# Base_USB_Camera.net
KiCad netlist of a schematic drawn in Altium Designer
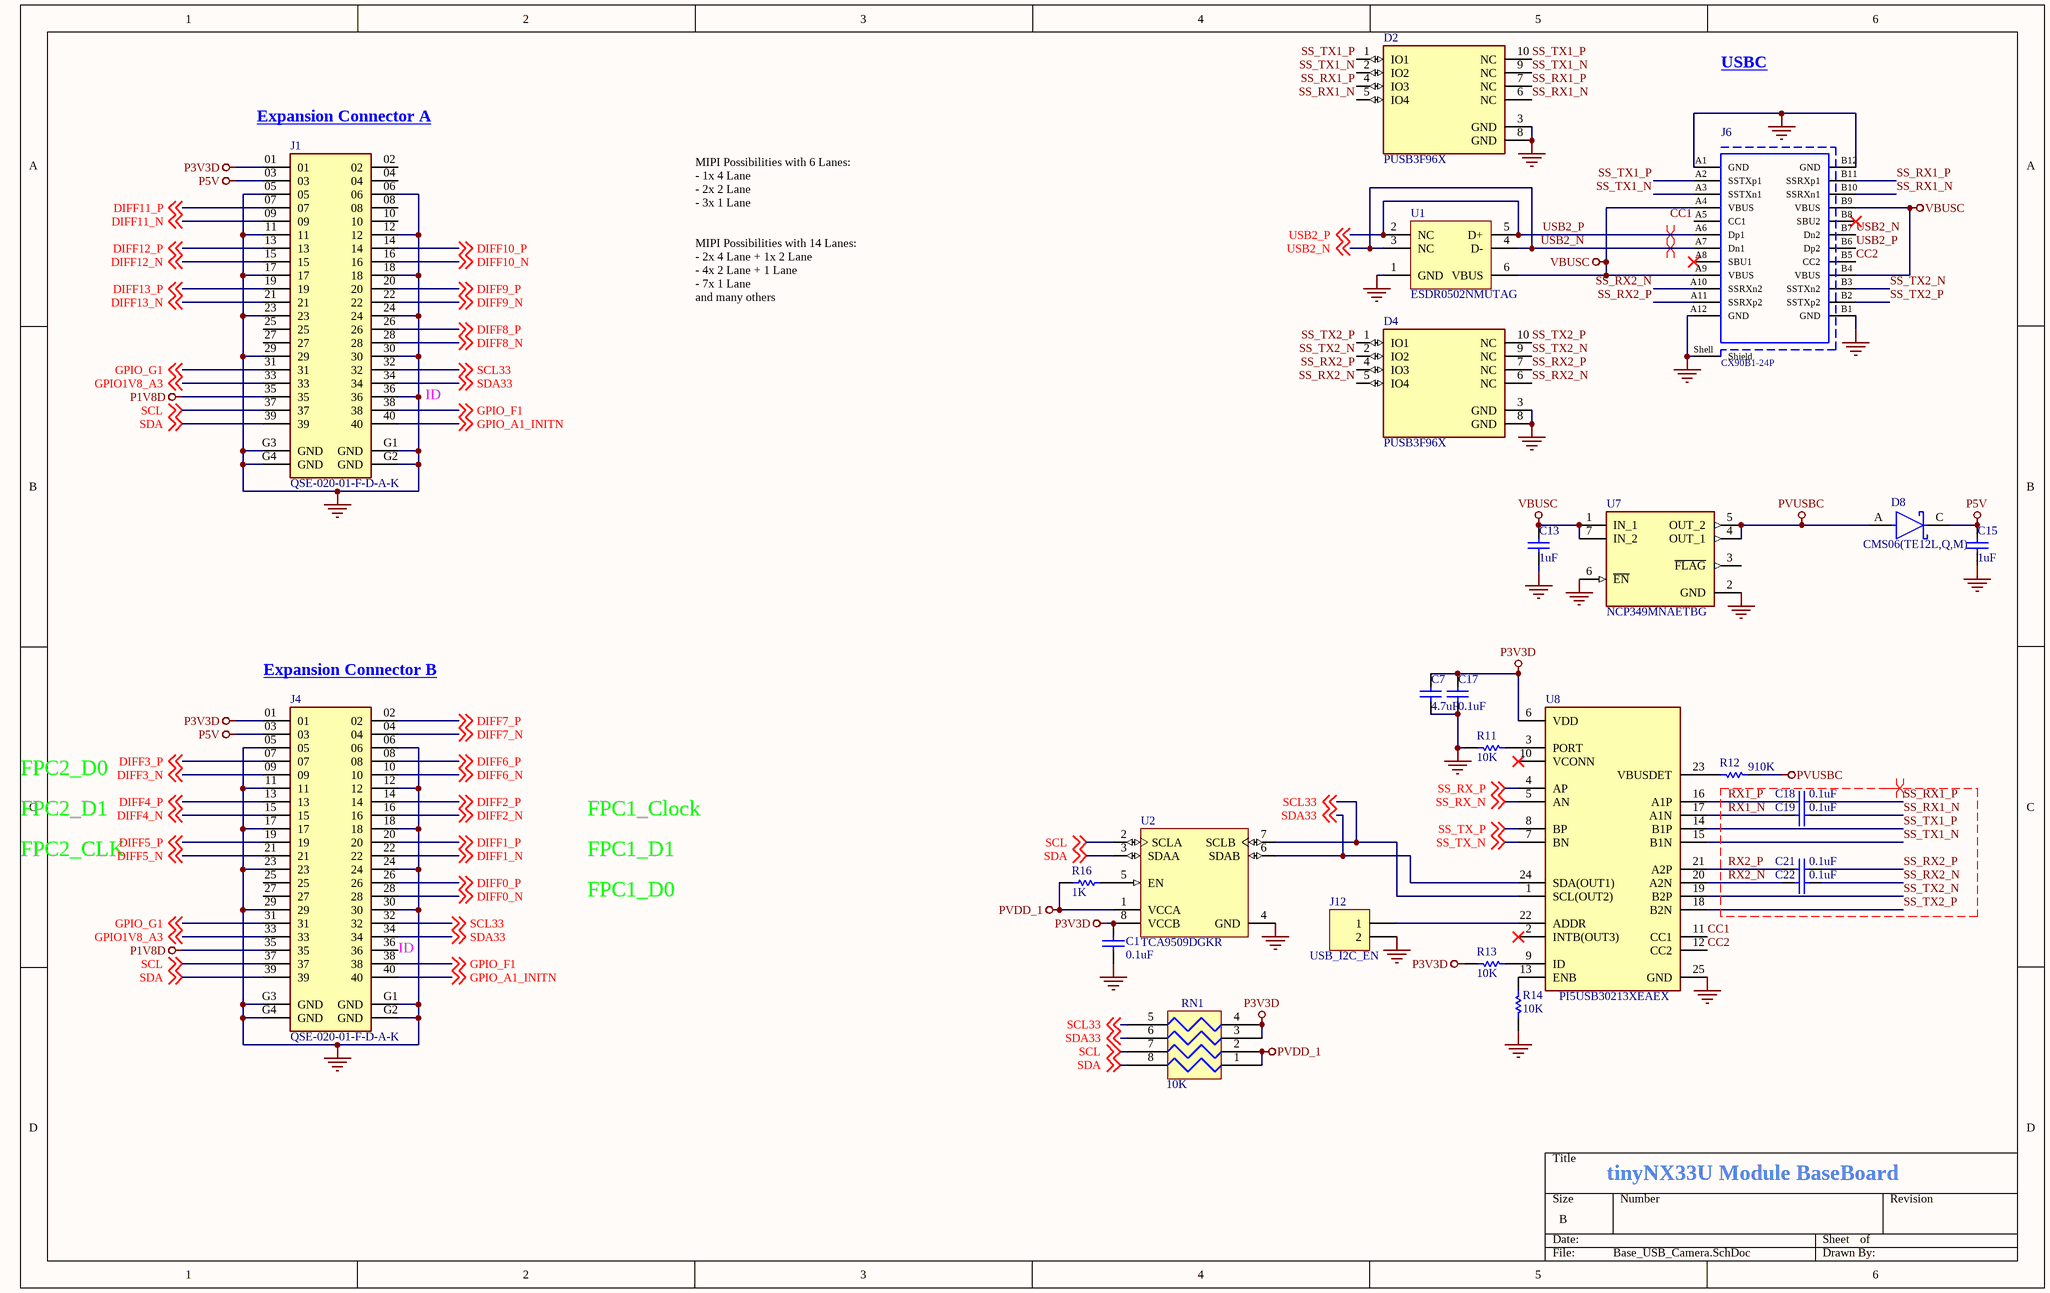
[diagram p0: Base_USB_Camera.SchDoc]

(export (version "E")
  (design (tool "Eeschema 10.0.6"))
  (components
    (comp (ref "C1")
      (value "0.1uF")
      (footprint "CAPC1005X55USR")
      (description "CAP CER 0.1UF 16V X7R 0402")
      (fields
        (field (name "MANUFACTURER PART NUMBER") "CGA2B1X7R1C104K050BC")
        (field (name "MANUFACTURER") "TDK Corporation")
      )
      (libsource (lib "NX Module baseboard") (part "CAP CER 0.1UF 16V X7R 0402"))
    )
    (comp (ref "C7")
      (value "4.7uF")
      (footprint "CAPC1005X55USR")
      (description "CAP CER 4.7UF 10V X5R 0402")
      (fields
        (field (name "MANUFACTURER PART NUMBER") "C1005X5R1A475M050BC")
        (field (name "MANUFACTURER") "TDK Corporation")
      )
      (libsource (lib "NX Module baseboard") (part "CAP CER 4.7UF 10V X5R 0402"))
    )
    (comp (ref "C13")
      (value "1uF")
      (footprint "CAPC1005X55USR")
      (description "CAP CER 1UF 25V X5R 0402")
      (fields
        (field (name "MANUFACTURER PART NUMBER") "GRM155R61E105MA12D")
        (field (name "MANUFACTURER") "Murata Electronics")
      )
      (libsource (lib "Tiger_Ti180") (part "CAP CER 1UF 25V X5R 0402"))
    )
    (comp (ref "C15")
      (value "1uF")
      (footprint "CAPC1005X55USR")
      (description "CAP CER 1UF 25V X5R 0402")
      (fields
        (field (name "MANUFACTURER PART NUMBER") "GRM155R61E105MA12D")
        (field (name "MANUFACTURER") "Murata Electronics")
      )
      (libsource (lib "Tiger_Ti180") (part "CAP CER 1UF 25V X5R 0402"))
    )
    (comp (ref "C17")
      (value "0.1uF")
      (footprint "CAPC1005X55USR")
      (description "CAP CER 0.1UF 16V X7R 0402")
      (fields
        (field (name "MANUFACTURER PART NUMBER") "CGA2B1X7R1C104K050BC")
        (field (name "MANUFACTURER") "TDK Corporation")
      )
      (libsource (lib "NX Module baseboard") (part "CAP CER 0.1UF 16V X7R 0402"))
    )
    (comp (ref "C18")
      (value "0.1uF")
      (footprint "CAPC1005X55USR")
      (description "CAP CER 0.1UF 16V X7R 0402")
      (fields
        (field (name "MANUFACTURER PART NUMBER") "CGA2B1X7R1C104K050BC")
        (field (name "MANUFACTURER") "TDK Corporation")
      )
      (libsource (lib "NX Module baseboard") (part "CAP CER 0.1UF 16V X7R 0402"))
    )
    (comp (ref "C19")
      (value "0.1uF")
      (footprint "CAPC1005X55USR")
      (description "CAP CER 0.1UF 16V X7R 0402")
      (fields
        (field (name "MANUFACTURER PART NUMBER") "CGA2B1X7R1C104K050BC")
        (field (name "MANUFACTURER") "TDK Corporation")
      )
      (libsource (lib "NX Module baseboard") (part "CAP CER 0.1UF 16V X7R 0402"))
    )
    (comp (ref "C21")
      (value "0.1uF")
      (footprint "CAPC1005X55USR")
      (description "CAP CER 0.1UF 16V X7R 0402")
      (fields
        (field (name "MANUFACTURER PART NUMBER") "CGA2B1X7R1C104K050BC")
        (field (name "MANUFACTURER") "TDK Corporation")
      )
      (libsource (lib "NX Module baseboard") (part "CAP CER 0.1UF 16V X7R 0402"))
    )
    (comp (ref "C22")
      (value "0.1uF")
      (footprint "CAPC1005X55USR")
      (description "CAP CER 0.1UF 16V X7R 0402")
      (fields
        (field (name "MANUFACTURER PART NUMBER") "CGA2B1X7R1C104K050BC")
        (field (name "MANUFACTURER") "TDK Corporation")
      )
      (libsource (lib "NX Module baseboard") (part "CAP CER 0.1UF 16V X7R 0402"))
    )
    (comp (ref "D2")
      (value "PUSB3F96X")
      (footprint "DFN2510A-10")
      (description "TVS DIODE 5.5VWM 4.6VC DFN2510A")
      (fields (field (name "MANUFACTURER") "Nexperia USA Inc."))
      (libsource (lib "Tiger_Ti180") (part "PUSB3F96X"))
    )
    (comp (ref "D4")
      (value "PUSB3F96X")
      (footprint "DFN2510A-10")
      (description "TVS DIODE 5.5VWM 4.6VC DFN2510A")
      (fields (field (name "MANUFACTURER") "Nexperia USA Inc."))
      (libsource (lib "Tiger_Ti180") (part "PUSB3F96X"))
    )
    (comp (ref "D8")
      (value "CMS06(TE12L,Q,M)")
      (footprint "SOD-128")
      (description "Rectifier Diode Schottky 30V 2A 2-Pin M-FLAT T/R")
      (fields (field (name "MANUFACTURER") "Toshiba"))
      (libsource (lib "Tiger_Ti180") (part "D_CMS06(TE12L,Q,M)"))
    )
    (comp (ref "J1")
      (value "QSE-020-01-F-D-A-K")
      (footprint "SAMTEC_QSE-020-01-XXX-D-A-L")
      (description "Q Strip® High-Speed Ground Plane Header, 0.80mm Pitch")
      (fields
        (field (name "MANUFACTURER") "Samtec")
        (field (name "MANUFACTURER PART NUMBER") "QTE-020-01-F-D-A")
      )
      (libsource (lib "NX Module baseboard") (part "QSE-020-01-F-D-A-K"))
    )
    (comp (ref "J4")
      (value "QSE-020-01-F-D-A-K")
      (footprint "SAMTEC_QSE-020-01-XXX-D-A-L")
      (description "Q Strip® High-Speed Ground Plane Header, 0.80mm Pitch")
      (fields
        (field (name "MANUFACTURER") "Samtec")
        (field (name "MANUFACTURER PART NUMBER") "QTE-020-01-F-D-A")
      )
      (libsource (lib "NX Module baseboard") (part "QSE-020-01-F-D-A-K"))
    )
    (comp (ref "J6")
      (value "CX90B1-24P")
      (footprint "HRS_CX90B1-24P")
      (description "CONN RCP USB3.1 TYPEC 24P SMD RA")
      (fields (field (name "MANUFACTURER") "Hirose Electric Co Ltd"))
      (libsource (lib "Tiger_Ti180") (part "USB 3.1_HRS_CX90B1-24P"))
    )
    (comp (ref "J12")
      (value "Header 2X1_2.54MM")
      (footprint "HDR2X1_MALE_2.54MM")
      (description "Conn Header Vert 2POS 2.54MM")
      (fields
        (field (name "MANUFACTURER") "Sullins")
        (field (name "MANUFACTURER PART NUMBER") "PRPC002SAAN-RC")
        (field (name "CONTENT") "USB_I2C_EN")
      )
      (libsource (lib "NX Module baseboard") (part "Header 2X1_2.54MM"))
    )
    (comp (ref "R11")
      (value "10K")
      (footprint "RESC1005X40USR")
      (description "RES SMD 10K OHM 1% 1/16W 0402")
      (fields
        (field (name "MANUFACTURER") "Samsung Electro-Mechanics")
        (field (name "MANUFACTURER PART NUMBER") "RC1005F103CS")
      )
      (libsource (lib "NX Module baseboard") (part "RES SMD 10K OHM 1% 1/16W 0402"))
    )
    (comp (ref "R12")
      (value "910K")
      (footprint "RESC1005X40USR")
      (description "RES 910K OHM 1% 1/16W 0402")
      (fields
        (field (name "MANUFACTURER") "YAGEO")
        (field (name "MANUFACTURER PART NUMBER") "RC0402FR-07910KL")
      )
      (libsource (lib "NX Module baseboard") (part "RES 910K OHM 1% 1/16W 0402"))
    )
    (comp (ref "R13")
      (value "10K")
      (footprint "RESC1005X40USR")
      (description "RES SMD 10K OHM 1% 1/16W 0402")
      (fields
        (field (name "MANUFACTURER") "Samsung Electro-Mechanics")
        (field (name "MANUFACTURER PART NUMBER") "RC1005F103CS")
      )
      (libsource (lib "NX Module baseboard") (part "RES SMD 10K OHM 1% 1/16W 0402"))
    )
    (comp (ref "R14")
      (value "10K")
      (footprint "RESC1005X40USR")
      (description "RES SMD 10K OHM 1% 1/16W 0402")
      (fields
        (field (name "MANUFACTURER") "Samsung Electro-Mechanics")
        (field (name "MANUFACTURER PART NUMBER") "RC1005F103CS")
      )
      (libsource (lib "NX Module baseboard") (part "RES SMD 10K OHM 1% 1/16W 0402"))
    )
    (comp (ref "R16")
      (value "1K")
      (footprint "RESC1005X40USR")
      (description "RES SMD 1K OHM 1% 1/16W 0402")
      (fields
        (field (name "MANUFACTURER") "YAGEO")
        (field (name "MANUFACTURER PART NUMBER") "RC0402FR-071KL")
      )
      (libsource (lib "Tiger_Ti180") (part "RES 1K OHM 1% 1/16W 0402"))
    )
    (comp (ref "RN1")
      (value "10K")
      (footprint "RESCAXS50P100X200X45-8NA")
      (description "Res Thick Film Array 10K Ohm 5% ±200ppm/°C ISOL 8-Pin 0804(4 X 0402) Convex SMD Automotive T/R")
      (fields
        (field (name "MANUFACTURER") "Panasonic")
        (field (name "MANUFACTURER PART NUMBER") "EXB-28V103JX")
      )
      (libsource (lib "NX Module") (part "RES ARRAY 4 RES 47K OHM 0804"))
    )
    (comp (ref "U1")
      (value "ESDR0502NMUTAG")
      (footprint "ONSC-UDFN-6-517AA-01_V")
      (description "TVS DIODE 5.5VWM 6UDFN")
      (fields (field (name "MANUFACTURER") "ON Semiconductor"))
      (libsource (lib "Tiger_Ti180") (part "ONSC-ESDR0502N-UDFN-6-517AA-01"))
    )
    (comp (ref "U2")
      (value "TCA9509DGKR")
      (footprint "SOP65P490X110-8N")
      (description "Level-translating I2C And Smbus")
      (fields (field (name "MANUFACTURER") "Texas Instruments"))
      (libsource (lib "NX Module") (part "TI-TCA9509-MSOP_DGK-8"))
    )
    (comp (ref "U7")
      (value "NCP349MNAETBG")
      (footprint "SON50P200X160X100-7N-D")
      (description "IC CTLR OVP 28V W/NMOS 6-DFN")
      (fields (field (name "MANUFACTURER") "ON Semiconductor"))
      (libsource (lib "Tiger_Ti180") (part "NCP349MNAETBG"))
    )
    (comp (ref "U8")
      (value "PI5USB30213XEAEX")
      (footprint "QFN40P400X200X50-25N")
      (description "USB Power SW DIST Single 2.7V to 5.5V 1.5A/3A 24-Pin TQFN T/R")
      (fields (field (name "MANUFACTURER") "Diodes"))
      (libsource (lib "NX Module baseboard") (part "PI5USB30213XEAEX"))
    )
  )
  (nets
    (net (code "1") (name "/CC1") (class "Default")
      (node (ref "J6") (pin "A5") (pinfunction "CC1_A5") (pintype "passive"))
      (node (ref "U8") (pin "11") (pinfunction "CC1_11") (pintype "passive"))
    )
    (net (code "2") (name "/CC2") (class "Default")
      (node (ref "J6") (pin "B5") (pinfunction "CC2_B5") (pintype "passive"))
      (node (ref "U8") (pin "12") (pinfunction "CC2_12") (pintype "passive"))
    )
    (net (code "3") (name "/RX1_N") (class "Default")
      (node (ref "C19") (pin "1") (pinfunction "1_1") (pintype "passive"))
      (node (ref "U8") (pin "17") (pinfunction "A1N_17") (pintype "passive"))
    )
    (net (code "4") (name "/RX1_P") (class "Default")
      (node (ref "C18") (pin "1") (pinfunction "1_1") (pintype "passive"))
      (node (ref "U8") (pin "16") (pinfunction "A1P_16") (pintype "passive"))
    )
    (net (code "5") (name "/RX2_N") (class "Default")
      (node (ref "C22") (pin "1") (pinfunction "1_1") (pintype "passive"))
      (node (ref "U8") (pin "20") (pinfunction "A2N_20") (pintype "passive"))
    )
    (net (code "6") (name "/RX2_P") (class "Default")
      (node (ref "C21") (pin "1") (pinfunction "1_1") (pintype "passive"))
      (node (ref "U8") (pin "21") (pinfunction "A2P_21") (pintype "passive"))
    )
    (net (code "7") (name "/SS_RX1_N") (class "Default")
      (node (ref "C19") (pin "2") (pinfunction "2_2") (pintype "passive"))
      (node (ref "D2") (pin "5") (pinfunction "IO4_5") (pintype "bidirectional"))
      (node (ref "D2") (pin "6") (pinfunction "NC_6") (pintype "passive"))
      (node (ref "J6") (pin "B10") (pinfunction "SSRXn1_B10") (pintype "passive"))
    )
    (net (code "8") (name "/SS_RX1_P") (class "Default")
      (node (ref "C18") (pin "2") (pinfunction "2_2") (pintype "passive"))
      (node (ref "D2") (pin "4") (pinfunction "IO3_4") (pintype "bidirectional"))
      (node (ref "D2") (pin "7") (pinfunction "NC_7") (pintype "passive"))
      (node (ref "J6") (pin "B11") (pinfunction "SSRXp1_B11") (pintype "passive"))
    )
    (net (code "9") (name "/SS_RX2_N") (class "Default")
      (node (ref "C22") (pin "2") (pinfunction "2_2") (pintype "passive"))
      (node (ref "D4") (pin "5") (pinfunction "IO4_5") (pintype "bidirectional"))
      (node (ref "D4") (pin "6") (pinfunction "NC_6") (pintype "passive"))
      (node (ref "J6") (pin "A10") (pinfunction "SSRXn2_A10") (pintype "passive"))
    )
    (net (code "10") (name "/SS_RX2_P") (class "Default")
      (node (ref "C21") (pin "2") (pinfunction "2_2") (pintype "passive"))
      (node (ref "D4") (pin "4") (pinfunction "IO3_4") (pintype "bidirectional"))
      (node (ref "D4") (pin "7") (pinfunction "NC_7") (pintype "passive"))
      (node (ref "J6") (pin "A11") (pinfunction "SSRXp2_A11") (pintype "passive"))
    )
    (net (code "11") (name "/SS_TX1_N") (class "Default")
      (node (ref "D2") (pin "2") (pinfunction "IO2_2") (pintype "bidirectional"))
      (node (ref "D2") (pin "9") (pinfunction "NC_9") (pintype "passive"))
      (node (ref "J6") (pin "A3") (pinfunction "SSTXn1_A3") (pintype "passive"))
      (node (ref "U8") (pin "15") (pinfunction "B1N_15") (pintype "passive"))
    )
    (net (code "12") (name "/SS_TX1_P") (class "Default")
      (node (ref "D2") (pin "1") (pinfunction "IO1_1") (pintype "bidirectional"))
      (node (ref "D2") (pin "10") (pinfunction "NC_10") (pintype "passive"))
      (node (ref "J6") (pin "A2") (pinfunction "SSTXp1_A2") (pintype "passive"))
      (node (ref "U8") (pin "14") (pinfunction "B1P_14") (pintype "passive"))
    )
    (net (code "13") (name "/SS_TX2_N") (class "Default")
      (node (ref "D4") (pin "2") (pinfunction "IO2_2") (pintype "bidirectional"))
      (node (ref "D4") (pin "9") (pinfunction "NC_9") (pintype "passive"))
      (node (ref "J6") (pin "B3") (pinfunction "SSTXn2_B3") (pintype "passive"))
      (node (ref "U8") (pin "19") (pinfunction "B2P_19") (pintype "passive"))
    )
    (net (code "14") (name "/SS_TX2_P") (class "Default")
      (node (ref "D4") (pin "1") (pinfunction "IO1_1") (pintype "bidirectional"))
      (node (ref "D4") (pin "10") (pinfunction "NC_10") (pintype "passive"))
      (node (ref "J6") (pin "B2") (pinfunction "SSTXp2_B2") (pintype "passive"))
      (node (ref "U8") (pin "18") (pinfunction "B2N_18") (pintype "passive"))
    )
    (net (code "15") (name "DIFF0_N") (class "Default")
      (node (ref "J4") (pin "28") (pinfunction "28_28") (pintype "passive"))
    )
    (net (code "16") (name "DIFF0_P") (class "Default")
      (node (ref "J4") (pin "26") (pinfunction "26_26") (pintype "passive"))
    )
    (net (code "17") (name "DIFF1_N") (class "Default")
      (node (ref "J4") (pin "22") (pinfunction "22_22") (pintype "passive"))
    )
    (net (code "18") (name "DIFF1_P") (class "Default")
      (node (ref "J4") (pin "20") (pinfunction "20_20") (pintype "passive"))
    )
    (net (code "19") (name "DIFF2_N") (class "Default")
      (node (ref "J4") (pin "16") (pinfunction "16_16") (pintype "passive"))
    )
    (net (code "20") (name "DIFF2_P") (class "Default")
      (node (ref "J4") (pin "14") (pinfunction "14_14") (pintype "passive"))
    )
    (net (code "21") (name "DIFF3_N") (class "Default")
      (node (ref "J4") (pin "09") (pinfunction "09_09") (pintype "passive"))
    )
    (net (code "22") (name "DIFF3_P") (class "Default")
      (node (ref "J4") (pin "07") (pinfunction "07_07") (pintype "passive"))
    )
    (net (code "23") (name "DIFF4_N") (class "Default")
      (node (ref "J4") (pin "15") (pinfunction "15_15") (pintype "passive"))
    )
    (net (code "24") (name "DIFF4_P") (class "Default")
      (node (ref "J4") (pin "13") (pinfunction "13_13") (pintype "passive"))
    )
    (net (code "25") (name "DIFF5_N") (class "Default")
      (node (ref "J4") (pin "21") (pinfunction "21_21") (pintype "passive"))
    )
    (net (code "26") (name "DIFF5_P") (class "Default")
      (node (ref "J4") (pin "19") (pinfunction "19_19") (pintype "passive"))
    )
    (net (code "27") (name "DIFF6_N") (class "Default")
      (node (ref "J4") (pin "10") (pinfunction "10_10") (pintype "passive"))
    )
    (net (code "28") (name "DIFF6_P") (class "Default")
      (node (ref "J4") (pin "08") (pinfunction "08_08") (pintype "passive"))
    )
    (net (code "29") (name "DIFF7_N") (class "Default")
      (node (ref "J4") (pin "04") (pinfunction "04_04") (pintype "passive"))
    )
    (net (code "30") (name "DIFF7_P") (class "Default")
      (node (ref "J4") (pin "02") (pinfunction "02_02") (pintype "passive"))
    )
    (net (code "31") (name "DIFF8_N") (class "Default")
      (node (ref "J1") (pin "28") (pinfunction "28_28") (pintype "passive"))
    )
    (net (code "32") (name "DIFF8_P") (class "Default")
      (node (ref "J1") (pin "26") (pinfunction "26_26") (pintype "passive"))
    )
    (net (code "33") (name "DIFF9_N") (class "Default")
      (node (ref "J1") (pin "22") (pinfunction "22_22") (pintype "passive"))
    )
    (net (code "34") (name "DIFF9_P") (class "Default")
      (node (ref "J1") (pin "20") (pinfunction "20_20") (pintype "passive"))
    )
    (net (code "35") (name "DIFF10_N") (class "Default")
      (node (ref "J1") (pin "16") (pinfunction "16_16") (pintype "passive"))
    )
    (net (code "36") (name "DIFF10_P") (class "Default")
      (node (ref "J1") (pin "14") (pinfunction "14_14") (pintype "passive"))
    )
    (net (code "37") (name "DIFF11_N") (class "Default")
      (node (ref "J1") (pin "09") (pinfunction "09_09") (pintype "passive"))
    )
    (net (code "38") (name "DIFF11_P") (class "Default")
      (node (ref "J1") (pin "07") (pinfunction "07_07") (pintype "passive"))
    )
    (net (code "39") (name "DIFF12_N") (class "Default")
      (node (ref "J1") (pin "15") (pinfunction "15_15") (pintype "passive"))
    )
    (net (code "40") (name "DIFF12_P") (class "Default")
      (node (ref "J1") (pin "13") (pinfunction "13_13") (pintype "passive"))
    )
    (net (code "41") (name "DIFF13_N") (class "Default")
      (node (ref "J1") (pin "21") (pinfunction "21_21") (pintype "passive"))
    )
    (net (code "42") (name "DIFF13_P") (class "Default")
      (node (ref "J1") (pin "19") (pinfunction "19_19") (pintype "passive"))
    )
    (net (code "43") (name "GND") (class "Default")
      (node (ref "C1") (pin "1") (pinfunction "1_1") (pintype "passive"))
      (node (ref "C13") (pin "1") (pinfunction "1_1") (pintype "passive"))
      (node (ref "C15") (pin "1") (pinfunction "1_1") (pintype "passive"))
      (node (ref "C17") (pin "1") (pinfunction "1_1") (pintype "passive"))
      (node (ref "C7") (pin "1") (pinfunction "1_1") (pintype "passive"))
      (node (ref "D2") (pin "3") (pinfunction "GND_3") (pintype "power_in"))
      (node (ref "D2") (pin "8") (pinfunction "GND_8") (pintype "power_in"))
      (node (ref "D4") (pin "3") (pinfunction "GND_3") (pintype "power_in"))
      (node (ref "D4") (pin "8") (pinfunction "GND_8") (pintype "power_in"))
      (node (ref "J1") (pin "05") (pinfunction "05_05") (pintype "passive"))
      (node (ref "J1") (pin "06") (pinfunction "06_06") (pintype "passive"))
      (node (ref "J1") (pin "11") (pinfunction "11_11") (pintype "passive"))
      (node (ref "J1") (pin "12") (pinfunction "12_12") (pintype "passive"))
      (node (ref "J1") (pin "17") (pinfunction "17_17") (pintype "passive"))
      (node (ref "J1") (pin "18") (pinfunction "18_18") (pintype "passive"))
      (node (ref "J1") (pin "23") (pinfunction "23_23") (pintype "passive"))
      (node (ref "J1") (pin "24") (pinfunction "24_24") (pintype "passive"))
      (node (ref "J1") (pin "29") (pinfunction "29_29") (pintype "passive"))
      (node (ref "J1") (pin "30") (pinfunction "30_30") (pintype "passive"))
      (node (ref "J1") (pin "36") (pinfunction "36_36") (pintype "passive"))
      (node (ref "J1") (pin "G1") (pinfunction "GND_G1") (pintype "power_in"))
      (node (ref "J1") (pin "G2") (pinfunction "GND_G2") (pintype "power_in"))
      (node (ref "J1") (pin "G3") (pinfunction "GND_G3") (pintype "power_in"))
      (node (ref "J1") (pin "G4") (pinfunction "GND_G4") (pintype "power_in"))
      (node (ref "J12") (pin "2") (pinfunction "2_2") (pintype "passive"))
      (node (ref "J4") (pin "05") (pinfunction "05_05") (pintype "passive"))
      (node (ref "J4") (pin "06") (pinfunction "06_06") (pintype "passive"))
      (node (ref "J4") (pin "11") (pinfunction "11_11") (pintype "passive"))
      (node (ref "J4") (pin "12") (pinfunction "12_12") (pintype "passive"))
      (node (ref "J4") (pin "17") (pinfunction "17_17") (pintype "passive"))
      (node (ref "J4") (pin "18") (pinfunction "18_18") (pintype "passive"))
      (node (ref "J4") (pin "23") (pinfunction "23_23") (pintype "passive"))
      (node (ref "J4") (pin "24") (pinfunction "24_24") (pintype "passive"))
      (node (ref "J4") (pin "29") (pinfunction "29_29") (pintype "passive"))
      (node (ref "J4") (pin "30") (pinfunction "30_30") (pintype "passive"))
      (node (ref "J4") (pin "G1") (pinfunction "GND_G1") (pintype "power_in"))
      (node (ref "J4") (pin "G2") (pinfunction "GND_G2") (pintype "power_in"))
      (node (ref "J4") (pin "G3") (pinfunction "GND_G3") (pintype "power_in"))
      (node (ref "J4") (pin "G4") (pinfunction "GND_G4") (pintype "power_in"))
      (node (ref "J6") (pin "A1") (pinfunction "GND_A1") (pintype "passive"))
      (node (ref "J6") (pin "A12") (pinfunction "GND_A12") (pintype "passive"))
      (node (ref "J6") (pin "B1") (pinfunction "GND_B1") (pintype "passive"))
      (node (ref "J6") (pin "B12") (pinfunction "GND_B12") (pintype "passive"))
      (node (ref "J6") (pin "Shell") (pinfunction "Shield_Shell") (pintype "passive"))
      (node (ref "R11") (pin "1") (pinfunction "1_1") (pintype "passive"))
      (node (ref "R14") (pin "2") (pinfunction "2_2") (pintype "passive"))
      (node (ref "U1") (pin "1") (pinfunction "GND_1") (pintype "power_in"))
      (node (ref "U2") (pin "4") (pinfunction "GND_4") (pintype "power_in"))
      (node (ref "U7") (pin "2") (pinfunction "GND_2") (pintype "power_in"))
      (node (ref "U7") (pin "6") (pinfunction "~{EN}_6") (pintype "input"))
      (node (ref "U8") (pin "25") (pinfunction "GND_25") (pintype "passive"))
    )
    (net (code "44") (name "GPIO1V8_A3") (class "Default")
      (node (ref "J1") (pin "33") (pinfunction "33_33") (pintype "passive"))
      (node (ref "J4") (pin "33") (pinfunction "33_33") (pintype "passive"))
    )
    (net (code "45") (name "GPIO_A1_INITN") (class "Default")
      (node (ref "J1") (pin "40") (pinfunction "40_40") (pintype "passive"))
      (node (ref "J4") (pin "40") (pinfunction "40_40") (pintype "passive"))
    )
    (net (code "46") (name "GPIO_F1") (class "Default")
      (node (ref "J1") (pin "38") (pinfunction "38_38") (pintype "passive"))
      (node (ref "J4") (pin "38") (pinfunction "38_38") (pintype "passive"))
    )
    (net (code "47") (name "GPIO_G1") (class "Default")
      (node (ref "J1") (pin "31") (pinfunction "31_31") (pintype "passive"))
      (node (ref "J4") (pin "31") (pinfunction "31_31") (pintype "passive"))
    )
    (net (code "48") (name "Net-(U2-EN)") (class "Default")
      (node (ref "R16") (pin "2") (pinfunction "2_2") (pintype "passive"))
      (node (ref "U2") (pin "5") (pinfunction "EN_5") (pintype "input"))
    )
    (net (code "49") (name "Net-(U8-ADDR)") (class "Default")
      (node (ref "J12") (pin "1") (pinfunction "1_1") (pintype "passive"))
      (node (ref "U8") (pin "22") (pinfunction "ADDR_22") (pintype "passive"))
    )
    (net (code "50") (name "Net-(U8-ENB)") (class "Default")
      (node (ref "R14") (pin "1") (pinfunction "1_1") (pintype "passive"))
      (node (ref "U8") (pin "13") (pinfunction "ENB_13") (pintype "passive"))
    )
    (net (code "51") (name "Net-(U8-ID)") (class "Default")
      (node (ref "R13") (pin "2") (pinfunction "2_2") (pintype "passive"))
      (node (ref "U8") (pin "9") (pinfunction "ID_9") (pintype "passive"))
    )
    (net (code "52") (name "Net-(U8-PORT)") (class "Default")
      (node (ref "R11") (pin "2") (pinfunction "2_2") (pintype "passive"))
      (node (ref "U8") (pin "3") (pinfunction "PORT_3") (pintype "passive"))
    )
    (net (code "53") (name "Net-(U8-VBUSDET)") (class "Default")
      (node (ref "R12") (pin "1") (pinfunction "1_1") (pintype "passive"))
      (node (ref "U8") (pin "23") (pinfunction "VBUSDET_23") (pintype "passive"))
    )
    (net (code "54") (name "P1V8D") (class "Default")
      (node (ref "J1") (pin "35") (pinfunction "35_35") (pintype "passive"))
      (node (ref "J4") (pin "35") (pinfunction "35_35") (pintype "passive"))
    )
    (net (code "55") (name "P3V3D") (class "Default")
      (node (ref "C1") (pin "2") (pinfunction "2_2") (pintype "passive"))
      (node (ref "C17") (pin "2") (pinfunction "2_2") (pintype "passive"))
      (node (ref "C7") (pin "2") (pinfunction "2_2") (pintype "passive"))
      (node (ref "J1") (pin "01") (pinfunction "01_01") (pintype "passive"))
      (node (ref "J4") (pin "01") (pinfunction "01_01") (pintype "passive"))
      (node (ref "R13") (pin "1") (pinfunction "1_1") (pintype "passive"))
      (node (ref "RN1") (pin "3") (pintype "passive"))
      (node (ref "RN1") (pin "4") (pintype "passive"))
      (node (ref "U2") (pin "8") (pinfunction "VCCB_8") (pintype "power_in"))
      (node (ref "U8") (pin "6") (pinfunction "VDD_6") (pintype "passive"))
    )
    (net (code "56") (name "P5V") (class "Default")
      (node (ref "C15") (pin "2") (pinfunction "2_2") (pintype "passive"))
      (node (ref "D8") (pin "C") (pinfunction "C_C") (pintype "passive"))
      (node (ref "J1") (pin "03") (pinfunction "03_03") (pintype "passive"))
      (node (ref "J4") (pin "03") (pinfunction "03_03") (pintype "passive"))
    )
    (net (code "57") (name "PVDD_1") (class "Default")
      (node (ref "R16") (pin "1") (pinfunction "1_1") (pintype "passive"))
      (node (ref "RN1") (pin "1") (pintype "passive"))
      (node (ref "RN1") (pin "2") (pintype "passive"))
      (node (ref "U2") (pin "1") (pinfunction "VCCA_1") (pintype "power_in"))
    )
    (net (code "58") (name "PVUSBC") (class "Default")
      (node (ref "D8") (pin "A") (pinfunction "A_A") (pintype "passive"))
      (node (ref "R12") (pin "2") (pinfunction "2_2") (pintype "passive"))
      (node (ref "U7") (pin "4") (pinfunction "OUT_1_4") (pintype "output"))
      (node (ref "U7") (pin "5") (pinfunction "OUT_2_5") (pintype "output"))
    )
    (net (code "59") (name "SCL") (class "Default")
      (node (ref "J1") (pin "37") (pinfunction "37_37") (pintype "passive"))
      (node (ref "J4") (pin "37") (pinfunction "37_37") (pintype "passive"))
      (node (ref "RN1") (pin "7") (pintype "passive"))
      (node (ref "U2") (pin "2") (pinfunction "SCLA_2") (pintype "bidirectional"))
    )
    (net (code "60") (name "SCL33") (class "Default")
      (node (ref "J1") (pin "32") (pinfunction "32_32") (pintype "passive"))
      (node (ref "J4") (pin "32") (pinfunction "32_32") (pintype "passive"))
      (node (ref "RN1") (pin "5") (pintype "passive"))
      (node (ref "U2") (pin "7") (pinfunction "SCLB_7") (pintype "bidirectional"))
      (node (ref "U8") (pin "1") (pinfunction "SCL(OUT2)_1") (pintype "passive"))
    )
    (net (code "61") (name "SDA") (class "Default")
      (node (ref "J1") (pin "39") (pinfunction "39_39") (pintype "passive"))
      (node (ref "J4") (pin "39") (pinfunction "39_39") (pintype "passive"))
      (node (ref "RN1") (pin "8") (pintype "passive"))
      (node (ref "U2") (pin "3") (pinfunction "SDAA_3") (pintype "bidirectional"))
    )
    (net (code "62") (name "SDA33") (class "Default")
      (node (ref "J1") (pin "34") (pinfunction "34_34") (pintype "passive"))
      (node (ref "J4") (pin "34") (pinfunction "34_34") (pintype "passive"))
      (node (ref "RN1") (pin "6") (pintype "passive"))
      (node (ref "U2") (pin "6") (pinfunction "SDAB_6") (pintype "bidirectional"))
      (node (ref "U8") (pin "24") (pinfunction "SDA(OUT1)_24") (pintype "passive"))
    )
    (net (code "63") (name "SS_RX_N") (class "Default")
      (node (ref "U8") (pin "5") (pinfunction "AN_5") (pintype "passive"))
    )
    (net (code "64") (name "SS_RX_P") (class "Default")
      (node (ref "U8") (pin "4") (pinfunction "AP_4") (pintype "passive"))
    )
    (net (code "65") (name "SS_TX_N") (class "Default")
      (node (ref "U8") (pin "7") (pinfunction "BN_7") (pintype "passive"))
    )
    (net (code "66") (name "SS_TX_P") (class "Default")
      (node (ref "U8") (pin "8") (pinfunction "BP_8") (pintype "passive"))
    )
    (net (code "67") (name "USB2_N") (class "Default")
      (node (ref "J6") (pin "A7") (pinfunction "Dn1_A7") (pintype "passive"))
      (node (ref "J6") (pin "B7") (pinfunction "Dn2_B7") (pintype "passive"))
      (node (ref "U1") (pin "3") (pinfunction "NC_3") (pintype "passive"))
      (node (ref "U1") (pin "4") (pinfunction "D-_4") (pintype "passive"))
    )
    (net (code "68") (name "USB2_P") (class "Default")
      (node (ref "J6") (pin "A6") (pinfunction "Dp1_A6") (pintype "passive"))
      (node (ref "J6") (pin "B6") (pinfunction "Dp2_B6") (pintype "passive"))
      (node (ref "U1") (pin "2") (pinfunction "NC_2") (pintype "passive"))
      (node (ref "U1") (pin "5") (pinfunction "D+_5") (pintype "passive"))
    )
    (net (code "69") (name "VBUSC") (class "Default")
      (node (ref "C13") (pin "2") (pinfunction "2_2") (pintype "passive"))
      (node (ref "J6") (pin "A4") (pinfunction "VBUS_A4") (pintype "passive"))
      (node (ref "J6") (pin "A9") (pinfunction "VBUS_A9") (pintype "passive"))
      (node (ref "J6") (pin "B4") (pinfunction "VBUS_B4") (pintype "passive"))
      (node (ref "J6") (pin "B9") (pinfunction "VBUS_B9") (pintype "passive"))
      (node (ref "U1") (pin "6") (pinfunction "VBUS_6") (pintype "power_in"))
      (node (ref "U7") (pin "1") (pinfunction "IN_1_1") (pintype "power_in"))
      (node (ref "U7") (pin "7") (pinfunction "IN_2_7") (pintype "power_in"))
    )
    (net (code "70") (name "unconnected-(J1-Pad02)") (class "Default")
      (node (ref "J1") (pin "02") (pinfunction "02_02") (pintype "passive"))
    )
    (net (code "71") (name "unconnected-(J1-Pad04)") (class "Default")
      (node (ref "J1") (pin "04") (pinfunction "04_04") (pintype "passive"))
    )
    (net (code "72") (name "unconnected-(J1-Pad08)") (class "Default")
      (node (ref "J1") (pin "08") (pinfunction "08_08") (pintype "passive"))
    )
    (net (code "73") (name "unconnected-(J1-Pad10)") (class "Default")
      (node (ref "J1") (pin "10") (pinfunction "10_10") (pintype "passive"))
    )
    (net (code "74") (name "unconnected-(J1-Pad25)") (class "Default")
      (node (ref "J1") (pin "25") (pinfunction "25_25") (pintype "passive"))
    )
    (net (code "75") (name "unconnected-(J1-Pad27)") (class "Default")
      (node (ref "J1") (pin "27") (pinfunction "27_27") (pintype "passive"))
    )
    (net (code "76") (name "unconnected-(J4-Pad25)") (class "Default")
      (node (ref "J4") (pin "25") (pinfunction "25_25") (pintype "passive"))
    )
    (net (code "77") (name "unconnected-(J4-Pad27)") (class "Default")
      (node (ref "J4") (pin "27") (pinfunction "27_27") (pintype "passive"))
    )
    (net (code "78") (name "unconnected-(J4-Pad36)") (class "Default")
      (node (ref "J4") (pin "36") (pinfunction "36_36") (pintype "passive"))
    )
    (net (code "79") (name "unconnected-(J6-SBU1-PadA8)") (class "Default")
      (node (ref "J6") (pin "A8") (pinfunction "SBU1_A8") (pintype "passive+no_connect"))
    )
    (net (code "80") (name "unconnected-(J6-SBU2-PadB8)") (class "Default")
      (node (ref "J6") (pin "B8") (pinfunction "SBU2_B8") (pintype "passive+no_connect"))
    )
    (net (code "81") (name "unconnected-(U7-~{FLAG}-Pad3)") (class "Default")
      (node (ref "U7") (pin "3") (pinfunction "~{FLAG}_3") (pintype "output"))
    )
    (net (code "82") (name "unconnected-(U8-INTB(OUT3)-Pad2)") (class "Default")
      (node (ref "U8") (pin "2") (pinfunction "INTB(OUT3)_2") (pintype "passive+no_connect"))
    )
    (net (code "83") (name "unconnected-(U8-VCONN-Pad10)") (class "Default")
      (node (ref "U8") (pin "10") (pinfunction "VCONN_10") (pintype "passive+no_connect"))
    )
  )
)
